# 01.net
KiCad netlist of a schematic drawn in EAGLE
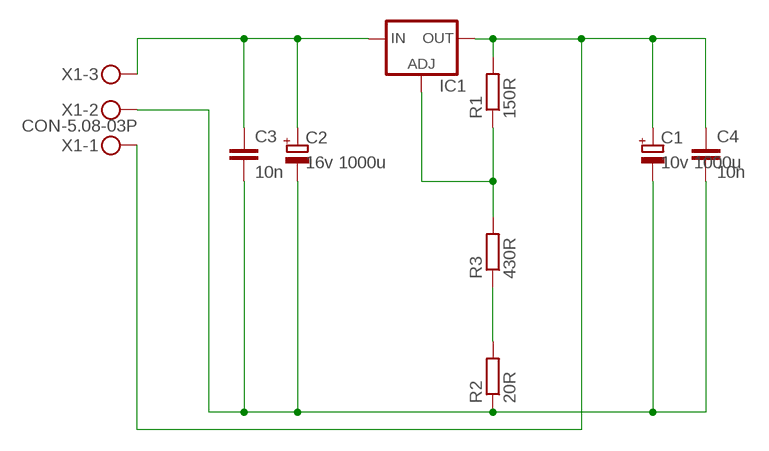
[diagram p0: schematic, sheet 1]

(export (version "E")
  (design (tool "Eeschema 10.0.6"))
  (components
    (comp (ref "C1")
      (value "10v 1000u")
      (footprint "eagle-import:E5-10,5")
      (libsource (lib "eagle-import") (part "CAP-POL_E5-10.5"))
    )
    (comp (ref "C2")
      (value "16v 1000u")
      (footprint "eagle-import:E5-10,5")
      (libsource (lib "eagle-import") (part "CAP-POL_E5-10.5"))
    )
    (comp (ref "C3")
      (value "10n")
      (footprint "eagle-import:C1206")
      (libsource (lib "eagle-import") (part "CAP_1206"))
    )
    (comp (ref "C4")
      (value "10n")
      (footprint "eagle-import:C1206")
      (libsource (lib "eagle-import") (part "CAP_1206"))
    )
    (comp (ref "IC1")
      (value "LM350T")
      (footprint "eagle-import:317TS")
      (libsource (lib "eagle-import") (part "LM350T"))
    )
    (comp (ref "R1")
      (value "150R")
      (footprint "eagle-import:R1206")
      (libsource (lib "eagle-import") (part "R_1206"))
    )
    (comp (ref "R2")
      (value "20R")
      (footprint "eagle-import:R1206")
      (libsource (lib "eagle-import") (part "R_1206"))
    )
    (comp (ref "R3")
      (value "430R")
      (footprint "eagle-import:R0805")
      (libsource (lib "eagle-import") (part "R_0805"))
    )
    (comp (ref "X1")
      (value "CON-5.08-03P")
      (footprint "eagle-import:MKDSN1,5_3-5,08")
      (libsource (lib "eagle-import") (part "CON-5.08-03P"))
    )
  )
  (nets
    (net (code "1") (name "Net-(IC1-ADJ)") (class "Default")
      (node (ref "IC1") (pin "1") (pinfunction "ADJ_1") (pintype "input"))
      (node (ref "R1") (pin "1") (pinfunction "1_1") (pintype "passive"))
      (node (ref "R3") (pin "2") (pinfunction "2_2") (pintype "passive"))
    )
    (net (code "2") (name "Net-(IC1-IN)") (class "Default")
      (node (ref "C2") (pin "+") (pinfunction "+_+") (pintype "passive"))
      (node (ref "C3") (pin "1") (pinfunction "1_1") (pintype "passive"))
      (node (ref "IC1") (pin "3") (pinfunction "IN_3") (pintype "input"))
      (node (ref "X1") (pin "3") (pinfunction "KL_3") (pintype "passive"))
    )
    (net (code "3") (name "Net-(IC1-OUT)") (class "Default")
      (node (ref "C1") (pin "+") (pinfunction "+_+") (pintype "passive"))
      (node (ref "C4") (pin "1") (pinfunction "1_1") (pintype "passive"))
      (node (ref "IC1") (pin "2") (pinfunction "OUT_2") (pintype "passive"))
      (node (ref "R1") (pin "2") (pinfunction "2_2") (pintype "passive"))
      (node (ref "X1") (pin "1") (pinfunction "KL_1") (pintype "passive"))
    )
    (net (code "4") (name "Net-(R2-Pad2)") (class "Default")
      (node (ref "R2") (pin "2") (pinfunction "2_2") (pintype "passive"))
      (node (ref "R3") (pin "1") (pinfunction "1_1") (pintype "passive"))
    )
    (net (code "5") (name "Net-(X1B-KL)") (class "Default")
      (node (ref "C1") (pin "-") (pinfunction "-_-") (pintype "passive"))
      (node (ref "C2") (pin "-") (pinfunction "-_-") (pintype "passive"))
      (node (ref "C3") (pin "2") (pinfunction "2_2") (pintype "passive"))
      (node (ref "C4") (pin "2") (pinfunction "2_2") (pintype "passive"))
      (node (ref "R2") (pin "1") (pinfunction "1_1") (pintype "passive"))
      (node (ref "X1") (pin "2") (pinfunction "KL_2") (pintype "passive"))
    )
  )
)
